# USB_Interface.net
KiCad netlist of a schematic drawn in Altium Designer
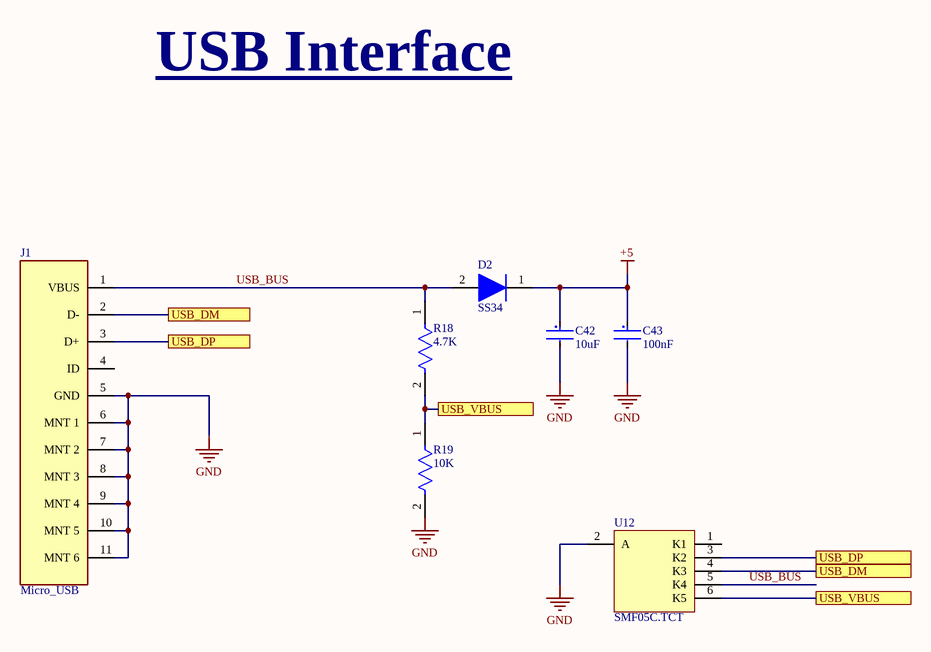
[diagram p0: USB_Interface.SchDoc]

(export (version "E")
  (design (tool "Eeschema 10.0.6"))
  (components
    (comp (ref "C42")
      (value "10uF")
      (footprint "Samsung_CL31_IPC_A_1206")
      (description "CAP CER 10UF 6.3V X5R 1206, ±10% 6.3V Ceramic Capacitor X5R 1206 (3216 Metric)")
      (libsource (lib "DMD_Card") (part "CL31A106KQHNNWE"))
    )
    (comp (ref "C43")
      (value "100nF")
      (footprint "Samsung_CL31_IPC_A_1206")
      (description "CAP CER 0.1UF 50V X7R 1206, ±10% 50V Ceramic Capacitor X7R 1206 (3216 Metric)")
      (libsource (lib "DMD_Card") (part "CL31B104KBCNFNC"))
    )
    (comp (ref "D2")
      (value "SS34")
      (footprint "SMA (DO-214AC)")
      (description "Rectifier, 2-Pin Axial_Lead, Pb-Free, Tape and Reel")
      (fields (field (name "MANUFACTURER") "On Semiconductor") (field (name "PARTNUMBER") "1N5819RLG"))
      (libsource (lib "DMD_Card") (part "1N5819RLG"))
    )
    (comp (ref "J1")
      (value "Micro_USB")
      (footprint "Micro_USB_47346- 1001")
      (description "CONN RCPT USB2.0 MICRO B SMD R/A")
      (libsource (lib "DMD_Card") (part "Micro_USB_47346-1001"))
    )
    (comp (ref "R18")
      (value "4.7K")
      (footprint "YAGEO_RC1206-0_65_IPC_A")
      (description "1 ±5% 0.25W, 1/4W Chip Resistor 1206 (3216 Metric) Moisture Resistant Thick Film")
      (libsource (lib "DMD_Card") (part "RC1206JR-071KL"))
    )
    (comp (ref "R19")
      (value "10K")
      (footprint "YAGEO_RC1206-0_65_IPC_A")
      (fields
        (field (name "MANUFACTURER") "Yageo")
        (field (name "MANUFACTURER PART NUMBER") "RC1206FR-072K2L")
        (field (name "TOLERANCE") "1%")
      )
      (libsource (lib "DMD_Card") (part "RC1206FR-072K2L"))
    )
    (comp (ref "U12")
      (value "SMF05C.TCT")
      (footprint "ONSC-SC70-6-419B-02_W_V")
      (description "ESD Suppressor TVS 15KV 6-Pin SC-70 T/R")
      (fields (field (name "MANUFACTURER") "Semtech"))
      (libsource (lib "DMD_Card") (part "SMF05C.TCT"))
    )
  )
  (nets
    (net (code "1") (name "+5") (class "Default")
      (node (ref "C42") (pin "1") (pinfunction "1_1") (pintype "passive"))
      (node (ref "C43") (pin "1") (pinfunction "1_1") (pintype "passive"))
      (node (ref "D2") (pin "1") (pinfunction "K_1") (pintype "passive"))
    )
    (net (code "2") (name "/USB_BUS") (class "Default")
      (node (ref "D2") (pin "2") (pinfunction "A_2") (pintype "passive"))
      (node (ref "J1") (pin "1") (pinfunction "VBUS_1") (pintype "power_in"))
      (node (ref "R18") (pin "1") (pinfunction "1_1") (pintype "passive"))
      (node (ref "U12") (pin "5") (pinfunction "K4_5") (pintype "passive"))
    )
    (net (code "3") (name "/USB_DM") (class "Default")
      (node (ref "J1") (pin "2") (pinfunction "D-_2") (pintype "passive"))
      (node (ref "U12") (pin "4") (pinfunction "K3_4") (pintype "passive"))
    )
    (net (code "4") (name "/USB_DP") (class "Default")
      (node (ref "J1") (pin "3") (pinfunction "D+_3") (pintype "passive"))
      (node (ref "U12") (pin "3") (pinfunction "K2_3") (pintype "passive"))
    )
    (net (code "5") (name "/USB_VBUS") (class "Default")
      (node (ref "R18") (pin "2") (pinfunction "2_2") (pintype "passive"))
      (node (ref "R19") (pin "1") (pinfunction "1_1") (pintype "passive"))
      (node (ref "U12") (pin "6") (pinfunction "K5_6") (pintype "passive"))
    )
    (net (code "6") (name "GND") (class "Default")
      (node (ref "C42") (pin "2") (pinfunction "2_2") (pintype "passive"))
      (node (ref "C43") (pin "2") (pinfunction "2_2") (pintype "passive"))
      (node (ref "J1") (pin "10") (pinfunction "MNT_5_10") (pintype "passive"))
      (node (ref "J1") (pin "11") (pinfunction "MNT_6_11") (pintype "passive"))
      (node (ref "J1") (pin "5") (pinfunction "GND_5") (pintype "power_in"))
      (node (ref "J1") (pin "6") (pinfunction "MNT_1_6") (pintype "passive"))
      (node (ref "J1") (pin "7") (pinfunction "MNT_2_7") (pintype "passive"))
      (node (ref "J1") (pin "8") (pinfunction "MNT_3_8") (pintype "passive"))
      (node (ref "J1") (pin "9") (pinfunction "MNT_4_9") (pintype "passive"))
      (node (ref "R19") (pin "2") (pinfunction "2_2") (pintype "passive"))
      (node (ref "U12") (pin "2") (pinfunction "A_2") (pintype "passive"))
    )
    (net (code "7") (name "unconnected-(J1-ID-Pad4)") (class "Default")
      (node (ref "J1") (pin "4") (pinfunction "ID_4") (pintype "passive"))
    )
    (net (code "8") (name "unconnected-(U12-K1-Pad1)") (class "Default")
      (node (ref "U12") (pin "1") (pinfunction "K1_1") (pintype "passive"))
    )
  )
)
